# CPU_IO.net
KiCad netlist of a schematic drawn in Altium Designer
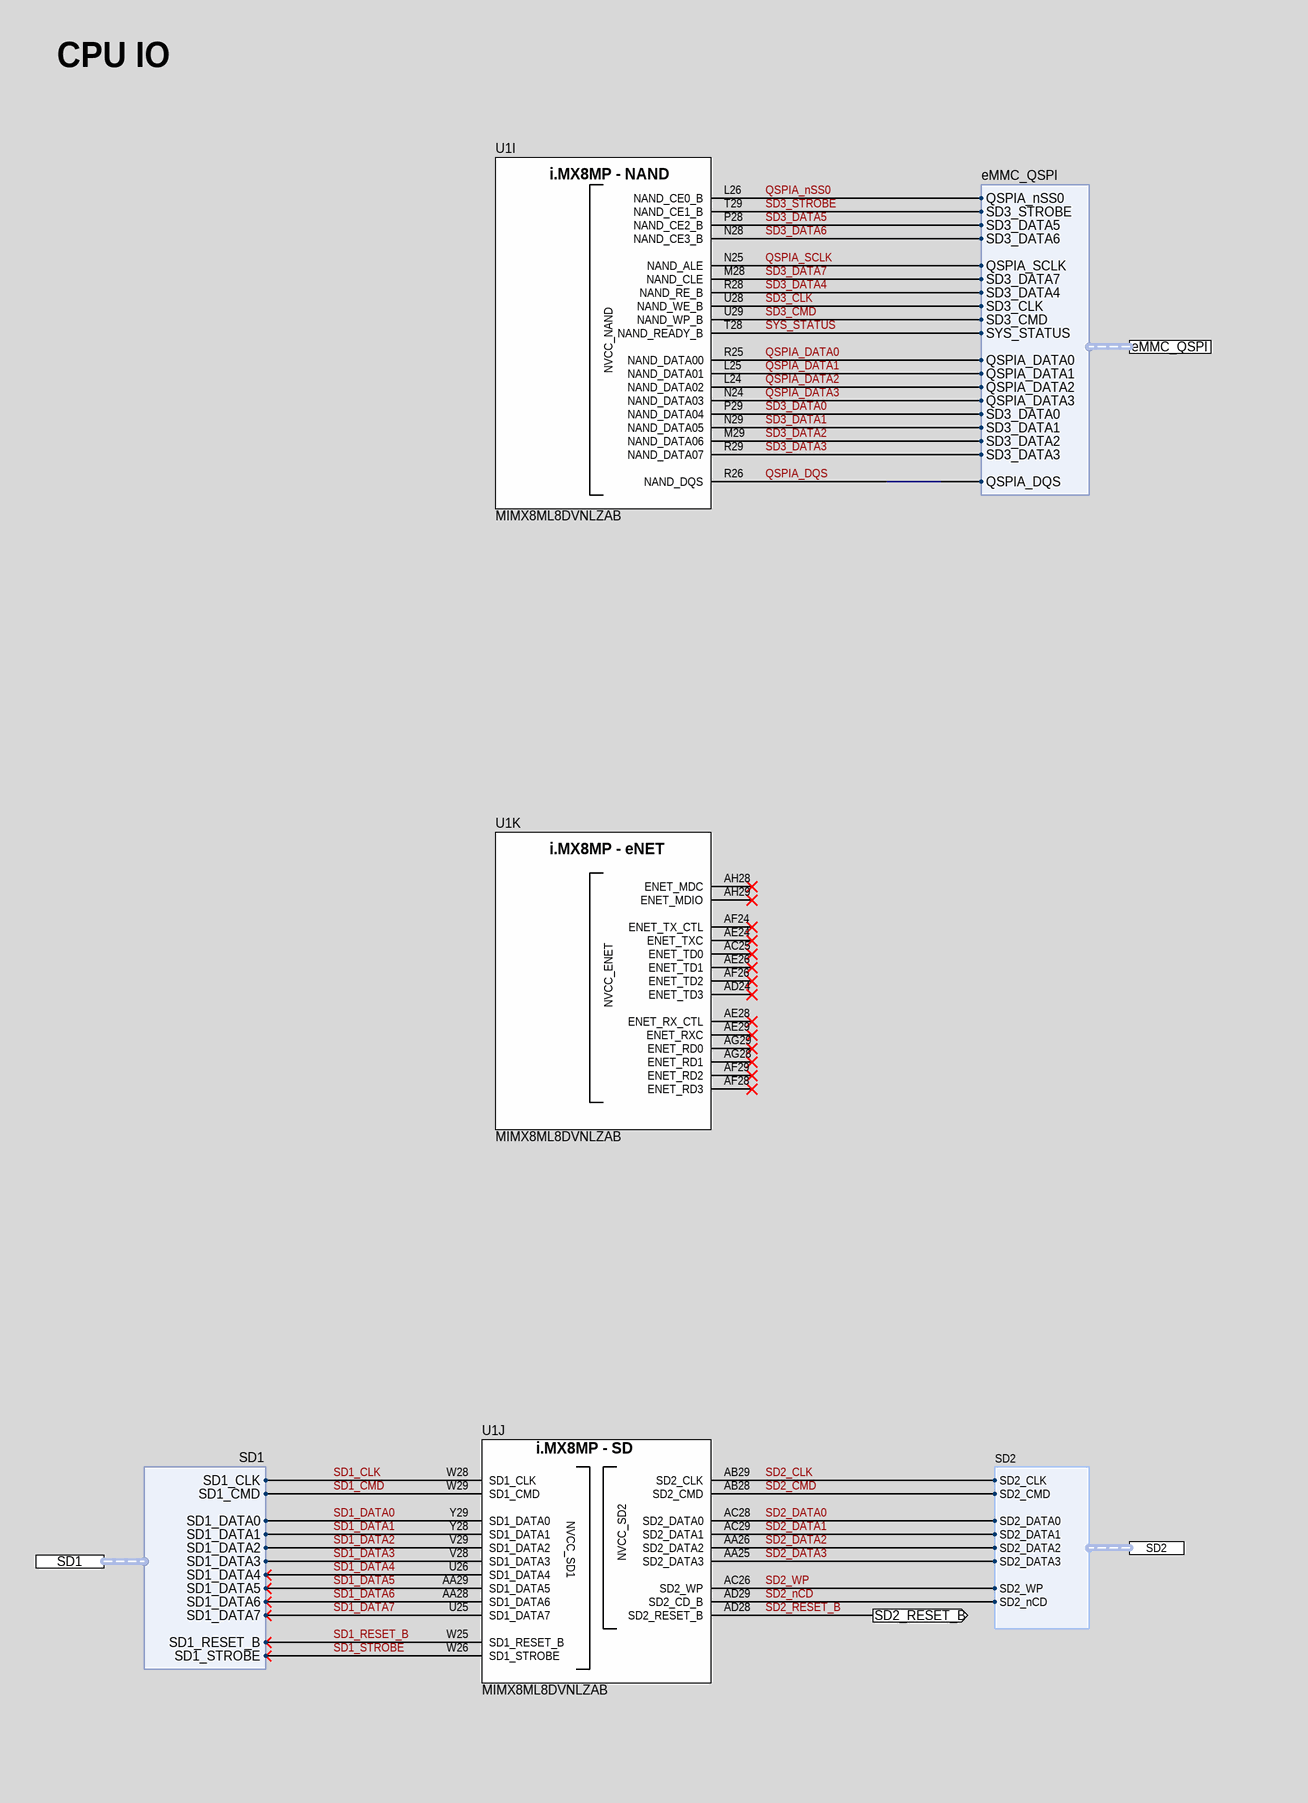
[diagram p0: CPU IO.SchDoc, left]
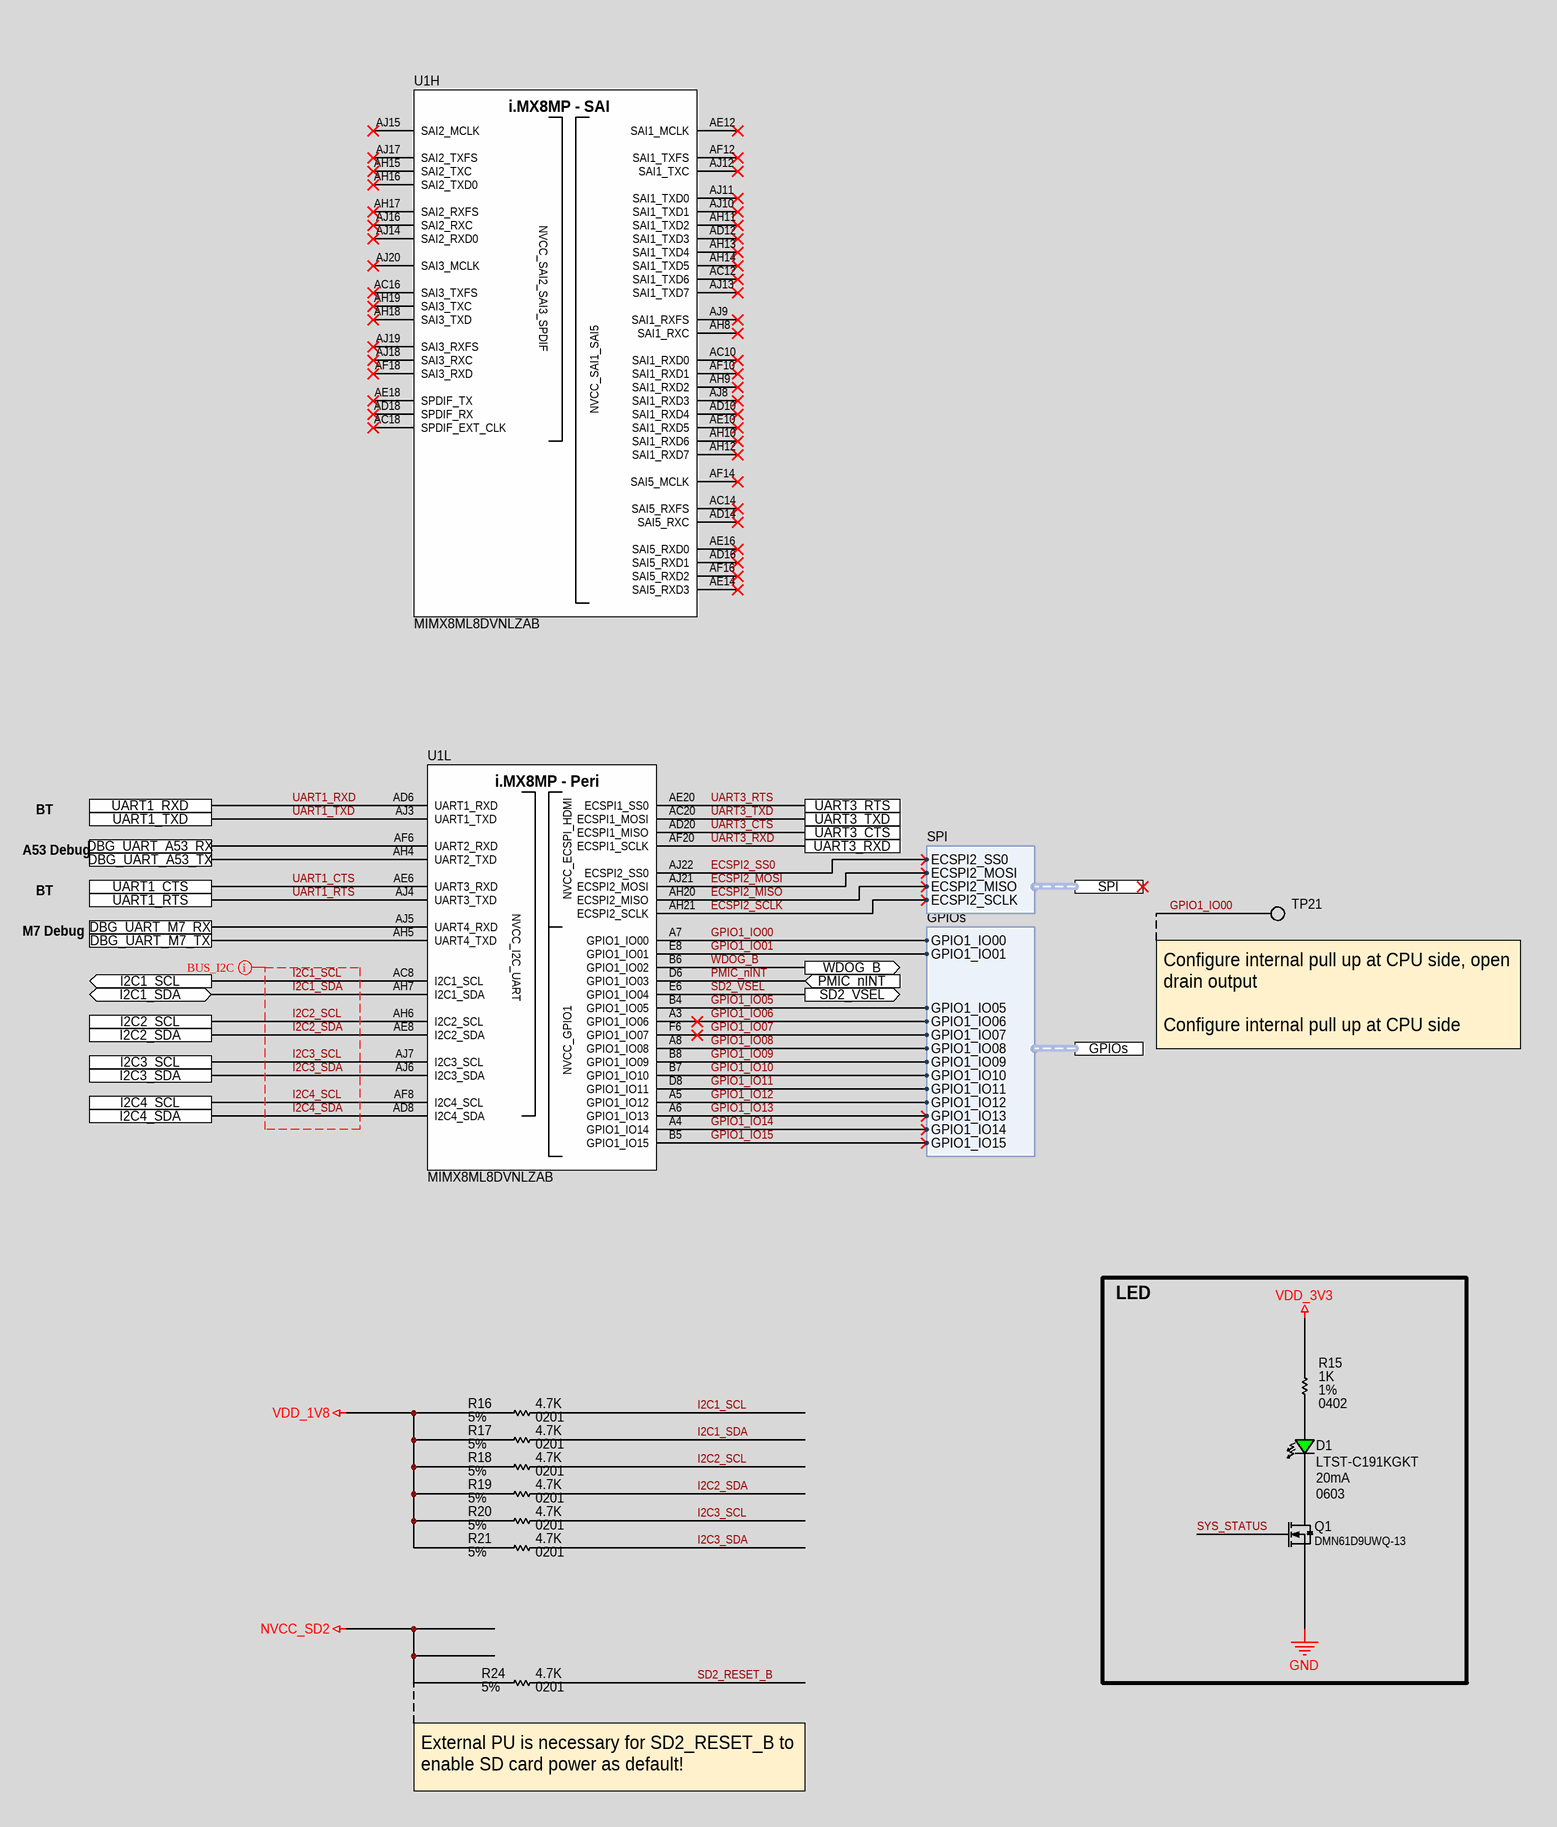
[diagram p1: CPU IO.SchDoc, right]

(export (version "E")
  (design (tool "Eeschema 10.0.6"))
  (components
    (comp (ref "D1")
      (value "LTST-C191KGKT")
      (footprint "LED_0603-GREEN")
      (description "LTST-C191KGKT Lite-On LED, green, 18-71mcd, 130, 1.9V-2.4V SMD, 0603 1.6x0.8x0.55mm RoHS")
      (fields
        (field (name "MANUFACTURER") "Vishay Lite-On")
        (field (name "TEST CURRENT") "20mA")
        (field (name "CASE/PACKAGE") "0603")
      )
      (libsource (lib "Electronic Devices_LIB") (part "LED_DIO_GREEN_20mA_0603"))
    )
    (comp (ref "Q1")
      (value "DMN61D9UWQ-13")
      (footprint "SOT-323")
      (description "N-Channel Enhancement Mode MOSFET 60V 340mA 3-Pin SOT-323 T/R")
      (fields (field (name "MANUFACTURER") "Diodes"))
      (libsource (lib "Electronic Devices_LIB") (part "TRANS_FET_CHA_N_60V_340mA"))
    )
    (comp (ref "R15")
      (value "ERJ-2RKF1001X")
      (footprint "RES_0402_RESC1005X04N")
      (description "RES SMD 1K OHM 1% 1/10W 0402")
      (fields
        (field (name "MANUFACTURER") "Panasonic")
        (field (name "RESISTANCE") "1K")
        (field (name "TOLERANCE") "1%")
        (field (name "CASE/PACKAGE") "0402")
      )
      (libsource (lib "Electronic Devices_LIB") (part "RES_1K_1%_100mW_0402"))
    )
    (comp (ref "R16")
      (value "RK73B1HTTC472J")
      (footprint "RES_0201_RESC0603X02N")
      (description "Res Thick Film 0201 4.7K Ohm 5% 0.05W(1/20W) ±200ppm/C Pad SMD Automotive T/R")
      (fields
        (field (name "MANUFACTURER") "KOA Speer")
        (field (name "TOLERANCE") "5%")
        (field (name "RESISTANCE") "4.7K")
        (field (name "CASE/PACKAGE") "0201")
      )
      (libsource (lib "Electronic Devices_LIB") (part "RES_4.7K_5%_50mW_0201"))
    )
    (comp (ref "R17")
      (value "RK73B1HTTC472J")
      (footprint "RES_0201_RESC0603X02N")
      (description "Res Thick Film 0201 4.7K Ohm 5% 0.05W(1/20W) ±200ppm/C Pad SMD Automotive T/R")
      (fields
        (field (name "MANUFACTURER") "KOA Speer")
        (field (name "TOLERANCE") "5%")
        (field (name "RESISTANCE") "4.7K")
        (field (name "CASE/PACKAGE") "0201")
      )
      (libsource (lib "Electronic Devices_LIB") (part "RES_4.7K_5%_50mW_0201"))
    )
    (comp (ref "R18")
      (value "RK73B1HTTC472J")
      (footprint "RES_0201_RESC0603X02N")
      (description "Res Thick Film 0201 4.7K Ohm 5% 0.05W(1/20W) ±200ppm/C Pad SMD Automotive T/R")
      (fields
        (field (name "MANUFACTURER") "KOA Speer")
        (field (name "TOLERANCE") "5%")
        (field (name "RESISTANCE") "4.7K")
        (field (name "CASE/PACKAGE") "0201")
      )
      (libsource (lib "Electronic Devices_LIB") (part "RES_4.7K_5%_50mW_0201"))
    )
    (comp (ref "R19")
      (value "RK73B1HTTC472J")
      (footprint "RES_0201_RESC0603X02N")
      (description "Res Thick Film 0201 4.7K Ohm 5% 0.05W(1/20W) ±200ppm/C Pad SMD Automotive T/R")
      (fields
        (field (name "MANUFACTURER") "KOA Speer")
        (field (name "TOLERANCE") "5%")
        (field (name "RESISTANCE") "4.7K")
        (field (name "CASE/PACKAGE") "0201")
      )
      (libsource (lib "Electronic Devices_LIB") (part "RES_4.7K_5%_50mW_0201"))
    )
    (comp (ref "R20")
      (value "RK73B1HTTC472J")
      (footprint "RES_0201_RESC0603X02N")
      (description "Res Thick Film 0201 4.7K Ohm 5% 0.05W(1/20W) ±200ppm/C Pad SMD Automotive T/R")
      (fields
        (field (name "MANUFACTURER") "KOA Speer")
        (field (name "TOLERANCE") "5%")
        (field (name "RESISTANCE") "4.7K")
        (field (name "CASE/PACKAGE") "0201")
      )
      (libsource (lib "Electronic Devices_LIB") (part "RES_4.7K_5%_50mW_0201"))
    )
    (comp (ref "R21")
      (value "RK73B1HTTC472J")
      (footprint "RES_0201_RESC0603X02N")
      (description "Res Thick Film 0201 4.7K Ohm 5% 0.05W(1/20W) ±200ppm/C Pad SMD Automotive T/R")
      (fields
        (field (name "MANUFACTURER") "KOA Speer")
        (field (name "TOLERANCE") "5%")
        (field (name "RESISTANCE") "4.7K")
        (field (name "CASE/PACKAGE") "0201")
      )
      (libsource (lib "Electronic Devices_LIB") (part "RES_4.7K_5%_50mW_0201"))
    )
    (comp (ref "R24")
      (value "RK73B1HTTC472J")
      (footprint "RES_0201_RESC0603X02N")
      (description "Res Thick Film 0201 4.7K Ohm 5% 0.05W(1/20W) ±200ppm/C Pad SMD Automotive T/R")
      (fields
        (field (name "MANUFACTURER") "KOA Speer")
        (field (name "TOLERANCE") "5%")
        (field (name "RESISTANCE") "4.7K")
        (field (name "CASE/PACKAGE") "0201")
      )
      (libsource (lib "Electronic Devices_LIB") (part "RES_4.7K_5%_50mW_0201"))
    )
    (comp (ref "TP21")
      (value "NO COMPONENT")
      (footprint "TP_PAD_0.5MM_SMD_ROUND")
      (description "Test Point, SMD pad, round, 1.5mm, 1.6mm, 3mm diameter")
      (libsource (lib "Electronic Devices_LIB") (part "TP_PAD_SMD_SMALL"))
    )
    (comp (ref "U1")
      (value "MIMX8ML8DVNLZAB")
      (footprint "IC_MPU_BGA548C50P29X29_1500X1500X148")
      (description "i.MX 8M Plus, Consumer, / TRAY TRAY MULTIPLE DP BAKEABLE RoHS Compliant: Yes")
      (fields (field (name "MANUFACTURER") "NXP Semiconductors"))
      (libsource (lib "Electronic Devices_LIB") (part "IC_MPU_8M_PLUS_MIMX8ML8DVNLZAB"))
    )
  )
  (nets
    (net (code "6") (name "/DBG_UART_A53_RX") (class "Default")
      (node (ref "U1") (pin "AF6") (pinfunction "UART2_RXD_AF6") (pintype "passive"))
    )
    (net (code "7") (name "/DBG_UART_A53_TX") (class "Default")
      (node (ref "U1") (pin "AH4") (pinfunction "UART2_TXD_AH4") (pintype "passive"))
    )
    (net (code "8") (name "/DBG_UART_M7_RX") (class "Default")
      (node (ref "U1") (pin "AJ5") (pinfunction "UART4_RXD_AJ5") (pintype "passive"))
    )
    (net (code "9") (name "/DBG_UART_M7_TX") (class "Default")
      (node (ref "U1") (pin "AH5") (pinfunction "UART4_TXD_AH5") (pintype "passive"))
    )
    (net (code "10") (name "/ECSPI2_MISO") (class "Default")
      (node (ref "U1") (pin "AH20") (pinfunction "ECSPI2_MISO_AH20") (pintype "passive+no_connect"))
    )
    (net (code "11") (name "/ECSPI2_MOSI") (class "Default")
      (node (ref "U1") (pin "AJ21") (pinfunction "ECSPI2_MOSI_AJ21") (pintype "passive+no_connect"))
    )
    (net (code "12") (name "/ECSPI2_SCLK") (class "Default")
      (node (ref "U1") (pin "AH21") (pinfunction "ECSPI2_SCLK_AH21") (pintype "passive+no_connect"))
    )
    (net (code "13") (name "/ECSPI2_SS0") (class "Default")
      (node (ref "U1") (pin "AJ22") (pinfunction "ECSPI2_SS0_AJ22") (pintype "passive+no_connect"))
    )
    (net (code "14") (name "/GPIO1_IO00") (class "Default")
      (node (ref "TP21") (pin "1") (pinfunction "1_1") (pintype "passive"))
      (node (ref "U1") (pin "A7") (pinfunction "GPIO1_IO00_A7") (pintype "passive"))
    )
    (net (code "15") (name "/GPIO1_IO01") (class "Default")
      (node (ref "U1") (pin "E8") (pinfunction "GPIO1_IO01_E8") (pintype "passive"))
    )
    (net (code "16") (name "/GPIO1_IO05") (class "Default")
      (node (ref "U1") (pin "B4") (pinfunction "GPIO1_IO05_B4") (pintype "passive"))
    )
    (net (code "17") (name "/GPIO1_IO06") (class "Default")
      (node (ref "U1") (pin "A3") (pinfunction "GPIO1_IO06_A3") (pintype "passive+no_connect"))
    )
    (net (code "18") (name "/GPIO1_IO07") (class "Default")
      (node (ref "U1") (pin "F6") (pinfunction "GPIO1_IO07_F6") (pintype "passive+no_connect"))
    )
    (net (code "19") (name "/GPIO1_IO08") (class "Default")
      (node (ref "U1") (pin "A8") (pinfunction "GPIO1_IO08_A8") (pintype "passive"))
    )
    (net (code "20") (name "/GPIO1_IO09") (class "Default")
      (node (ref "U1") (pin "B8") (pinfunction "GPIO1_IO09_B8") (pintype "passive"))
    )
    (net (code "21") (name "/GPIO1_IO10") (class "Default")
      (node (ref "U1") (pin "B7") (pinfunction "GPIO1_IO10_B7") (pintype "passive"))
    )
    (net (code "22") (name "/GPIO1_IO11") (class "Default")
      (node (ref "U1") (pin "D8") (pinfunction "GPIO1_IO11_D8") (pintype "passive"))
    )
    (net (code "23") (name "/GPIO1_IO12") (class "Default")
      (node (ref "U1") (pin "A5") (pinfunction "GPIO1_IO12_A5") (pintype "passive"))
    )
    (net (code "24") (name "/GPIO1_IO13") (class "Default")
      (node (ref "U1") (pin "A6") (pinfunction "GPIO1_IO13_A6") (pintype "passive+no_connect"))
    )
    (net (code "25") (name "/GPIO1_IO14") (class "Default")
      (node (ref "U1") (pin "A4") (pinfunction "GPIO1_IO14_A4") (pintype "passive+no_connect"))
    )
    (net (code "26") (name "/GPIO1_IO15") (class "Default")
      (node (ref "U1") (pin "B5") (pinfunction "GPIO1_IO15_B5") (pintype "passive+no_connect"))
    )
    (net (code "27") (name "/I2C1_SCL") (class "Default")
      (node (ref "R16") (pin "2") (pinfunction "2_2") (pintype "passive"))
      (node (ref "U1") (pin "AC8") (pinfunction "I2C1_SCL_AC8") (pintype "passive"))
    )
    (net (code "28") (name "/I2C1_SDA") (class "Default")
      (node (ref "R17") (pin "2") (pinfunction "2_2") (pintype "passive"))
      (node (ref "U1") (pin "AH7") (pinfunction "I2C1_SDA_AH7") (pintype "passive"))
    )
    (net (code "29") (name "/I2C2_SCL") (class "Default")
      (node (ref "R18") (pin "2") (pinfunction "2_2") (pintype "passive"))
      (node (ref "U1") (pin "AH6") (pinfunction "I2C2_SCL_AH6") (pintype "passive"))
    )
    (net (code "30") (name "/I2C2_SDA") (class "Default")
      (node (ref "R19") (pin "2") (pinfunction "2_2") (pintype "passive"))
      (node (ref "U1") (pin "AE8") (pinfunction "I2C2_SDA_AE8") (pintype "passive"))
    )
    (net (code "31") (name "/I2C3_SCL") (class "Default")
      (node (ref "R20") (pin "2") (pinfunction "2_2") (pintype "passive"))
      (node (ref "U1") (pin "AJ7") (pinfunction "I2C3_SCL_AJ7") (pintype "passive"))
    )
    (net (code "32") (name "/I2C3_SDA") (class "Default")
      (node (ref "R21") (pin "2") (pinfunction "2_2") (pintype "passive"))
      (node (ref "U1") (pin "AJ6") (pinfunction "I2C3_SDA_AJ6") (pintype "passive"))
    )
    (net (code "33") (name "/I2C4_SCL") (class "Default")
      (node (ref "U1") (pin "AF8") (pinfunction "I2C4_SCL_AF8") (pintype "passive"))
    )
    (net (code "34") (name "/I2C4_SDA") (class "Default")
      (node (ref "U1") (pin "AD8") (pinfunction "I2C4_SDA_AD8") (pintype "passive"))
    )
    (net (code "35") (name "/PMIC_nINT") (class "Default")
      (node (ref "U1") (pin "D6") (pinfunction "GPIO1_IO03_D6") (pintype "passive"))
    )
    (net (code "36") (name "/QSPIA_DATA0") (class "Default")
      (node (ref "U1") (pin "R25") (pinfunction "NAND_DATA00_R25") (pintype "passive"))
    )
    (net (code "37") (name "/QSPIA_DATA1") (class "Default")
      (node (ref "U1") (pin "L25") (pinfunction "NAND_DATA01_L25") (pintype "passive"))
    )
    (net (code "38") (name "/QSPIA_DATA2") (class "Default")
      (node (ref "U1") (pin "L24") (pinfunction "NAND_DATA02_L24") (pintype "passive"))
    )
    (net (code "39") (name "/QSPIA_DATA3") (class "Default")
      (node (ref "U1") (pin "N24") (pinfunction "NAND_DATA03_N24") (pintype "passive"))
    )
    (net (code "40") (name "/QSPIA_DQS") (class "Default")
      (node (ref "U1") (pin "R26") (pinfunction "NAND_DQS_R26") (pintype "passive"))
    )
    (net (code "41") (name "/QSPIA_SCLK") (class "Default")
      (node (ref "U1") (pin "N25") (pinfunction "NAND_ALE_N25") (pintype "passive"))
    )
    (net (code "42") (name "/QSPIA_nSS0") (class "Default")
      (node (ref "U1") (pin "L26") (pinfunction "NAND_CE0_B_L26") (pintype "passive"))
    )
    (net (code "43") (name "/SD1_CLK") (class "Default")
      (node (ref "U1") (pin "W28") (pinfunction "SD1_CLK_W28") (pintype "passive"))
    )
    (net (code "44") (name "/SD1_CMD") (class "Default")
      (node (ref "U1") (pin "W29") (pinfunction "SD1_CMD_W29") (pintype "passive"))
    )
    (net (code "45") (name "/SD1_DATA0") (class "Default")
      (node (ref "U1") (pin "Y29") (pinfunction "SD1_DATA0_Y29") (pintype "passive"))
    )
    (net (code "46") (name "/SD1_DATA1") (class "Default")
      (node (ref "U1") (pin "Y28") (pinfunction "SD1_DATA1_Y28") (pintype "passive"))
    )
    (net (code "47") (name "/SD1_DATA2") (class "Default")
      (node (ref "U1") (pin "V29") (pinfunction "SD1_DATA2_V29") (pintype "passive"))
    )
    (net (code "48") (name "/SD1_DATA3") (class "Default")
      (node (ref "U1") (pin "V28") (pinfunction "SD1_DATA3_V28") (pintype "passive"))
    )
    (net (code "49") (name "/SD1_DATA4") (class "Default")
      (node (ref "U1") (pin "U26") (pinfunction "SD1_DATA4_U26") (pintype "passive+no_connect"))
    )
    (net (code "50") (name "/SD1_DATA5") (class "Default")
      (node (ref "U1") (pin "AA29") (pinfunction "SD1_DATA5_AA29") (pintype "passive+no_connect"))
    )
    (net (code "51") (name "/SD1_DATA6") (class "Default")
      (node (ref "U1") (pin "AA28") (pinfunction "SD1_DATA6_AA28") (pintype "passive+no_connect"))
    )
    (net (code "52") (name "/SD1_DATA7") (class "Default")
      (node (ref "U1") (pin "U25") (pinfunction "SD1_DATA7_U25") (pintype "passive+no_connect"))
    )
    (net (code "53") (name "/SD1_RESET_B") (class "Default")
      (node (ref "U1") (pin "W25") (pinfunction "SD1_RESET_B_W25") (pintype "passive+no_connect"))
    )
    (net (code "54") (name "/SD1_STROBE") (class "Default")
      (node (ref "U1") (pin "W26") (pinfunction "SD1_STROBE_W26") (pintype "passive+no_connect"))
    )
    (net (code "55") (name "/SD2_CLK") (class "Default")
      (node (ref "U1") (pin "AB29") (pinfunction "SD2_CLK_AB29") (pintype "passive"))
    )
    (net (code "56") (name "/SD2_CMD") (class "Default")
      (node (ref "U1") (pin "AB28") (pinfunction "SD2_CMD_AB28") (pintype "passive"))
    )
    (net (code "57") (name "/SD2_DATA0") (class "Default")
      (node (ref "U1") (pin "AC28") (pinfunction "SD2_DATA0_AC28") (pintype "passive"))
    )
    (net (code "58") (name "/SD2_DATA1") (class "Default")
      (node (ref "U1") (pin "AC29") (pinfunction "SD2_DATA1_AC29") (pintype "passive"))
    )
    (net (code "59") (name "/SD2_DATA2") (class "Default")
      (node (ref "U1") (pin "AA26") (pinfunction "SD2_DATA2_AA26") (pintype "passive"))
    )
    (net (code "60") (name "/SD2_DATA3") (class "Default")
      (node (ref "U1") (pin "AA25") (pinfunction "SD2_DATA3_AA25") (pintype "passive"))
    )
    (net (code "61") (name "/SD2_RESET_B") (class "Default")
      (node (ref "R24") (pin "2") (pinfunction "2_2") (pintype "passive"))
      (node (ref "U1") (pin "AD28") (pinfunction "SD2_RESET_B_AD28") (pintype "passive"))
    )
    (net (code "62") (name "/SD2_VSEL") (class "Default")
      (node (ref "U1") (pin "E6") (pinfunction "GPIO1_IO04_E6") (pintype "passive"))
    )
    (net (code "63") (name "/SD2_WP") (class "Default")
      (node (ref "U1") (pin "AC26") (pinfunction "SD2_WP_AC26") (pintype "passive"))
    )
    (net (code "64") (name "/SD2_nCD") (class "Default")
      (node (ref "U1") (pin "AD29") (pinfunction "SD2_CD_B_AD29") (pintype "passive"))
    )
    (net (code "65") (name "/SD3_CLK") (class "Default")
      (node (ref "U1") (pin "U28") (pinfunction "NAND_WE_B_U28") (pintype "passive"))
    )
    (net (code "66") (name "/SD3_CMD") (class "Default")
      (node (ref "U1") (pin "U29") (pinfunction "NAND_WP_B_U29") (pintype "passive"))
    )
    (net (code "67") (name "/SD3_DATA0") (class "Default")
      (node (ref "U1") (pin "P29") (pinfunction "NAND_DATA04_P29") (pintype "passive"))
    )
    (net (code "68") (name "/SD3_DATA1") (class "Default")
      (node (ref "U1") (pin "N29") (pinfunction "NAND_DATA05_N29") (pintype "passive"))
    )
    (net (code "69") (name "/SD3_DATA2") (class "Default")
      (node (ref "U1") (pin "M29") (pinfunction "NAND_DATA06_M29") (pintype "passive"))
    )
    (net (code "70") (name "/SD3_DATA3") (class "Default")
      (node (ref "U1") (pin "R29") (pinfunction "NAND_DATA07_R29") (pintype "passive"))
    )
    (net (code "71") (name "/SD3_DATA4") (class "Default")
      (node (ref "U1") (pin "R28") (pinfunction "NAND_RE_B_R28") (pintype "passive"))
    )
    (net (code "72") (name "/SD3_DATA5") (class "Default")
      (node (ref "U1") (pin "P28") (pinfunction "NAND_CE2_B_P28") (pintype "passive"))
    )
    (net (code "73") (name "/SD3_DATA6") (class "Default")
      (node (ref "U1") (pin "N28") (pinfunction "NAND_CE3_B_N28") (pintype "passive"))
    )
    (net (code "74") (name "/SD3_DATA7") (class "Default")
      (node (ref "U1") (pin "M28") (pinfunction "NAND_CLE_M28") (pintype "passive"))
    )
    (net (code "75") (name "/SD3_STROBE") (class "Default")
      (node (ref "U1") (pin "T29") (pinfunction "NAND_CE1_B_T29") (pintype "passive"))
    )
    (net (code "76") (name "/SYS_STATUS") (class "Default")
      (node (ref "Q1") (pin "G") (pinfunction "G_G") (pintype "passive"))
      (node (ref "U1") (pin "T28") (pinfunction "NAND_READY_B_T28") (pintype "passive"))
    )
    (net (code "77") (name "/UART1_CTS") (class "Default")
      (node (ref "U1") (pin "AE6") (pinfunction "UART3_RXD_AE6") (pintype "passive"))
    )
    (net (code "78") (name "/UART1_RTS") (class "Default")
      (node (ref "U1") (pin "AJ4") (pinfunction "UART3_TXD_AJ4") (pintype "passive"))
    )
    (net (code "79") (name "/UART1_RXD") (class "Default")
      (node (ref "U1") (pin "AD6") (pinfunction "UART1_RXD_AD6") (pintype "passive"))
    )
    (net (code "80") (name "/UART1_TXD") (class "Default")
      (node (ref "U1") (pin "AJ3") (pinfunction "UART1_TXD_AJ3") (pintype "passive"))
    )
    (net (code "81") (name "/UART3_CTS") (class "Default")
      (node (ref "U1") (pin "AD20") (pinfunction "ECSPI1_MISO_AD20") (pintype "passive"))
    )
    (net (code "82") (name "/UART3_RTS") (class "Default")
      (node (ref "U1") (pin "AE20") (pinfunction "ECSPI1_SS0_AE20") (pintype "passive"))
    )
    (net (code "83") (name "/UART3_RXD") (class "Default")
      (node (ref "U1") (pin "AF20") (pinfunction "ECSPI1_SCLK_AF20") (pintype "passive"))
    )
    (net (code "84") (name "/UART3_TXD") (class "Default")
      (node (ref "U1") (pin "AC20") (pinfunction "ECSPI1_MOSI_AC20") (pintype "passive"))
    )
    (net (code "85") (name "/WDOG_B") (class "Default")
      (node (ref "U1") (pin "B6") (pinfunction "GPIO1_IO02_B6") (pintype "passive"))
    )
    (net (code "91") (name "GND") (class "Default")
      (node (ref "Q1") (pin "S") (pinfunction "S_S") (pintype "passive"))
    )
    (net (code "92") (name "NVCC_SD2") (class "Default")
      (node (ref "R24") (pin "1") (pinfunction "1_1") (pintype "passive"))
    )
    (net (code "93") (name "Net-(D1-A)") (class "Default")
      (node (ref "D1") (pin "2") (pinfunction "A_2") (pintype "passive"))
      (node (ref "R15") (pin "1") (pinfunction "1_1") (pintype "passive"))
    )
    (net (code "94") (name "Net-(D1-C)") (class "Default")
      (node (ref "D1") (pin "1") (pinfunction "C_1") (pintype "passive"))
      (node (ref "Q1") (pin "D") (pinfunction "D_D") (pintype "passive"))
    )
    (net (code "95") (name "VDD_1V8") (class "Default")
      (node (ref "R16") (pin "1") (pinfunction "1_1") (pintype "passive"))
      (node (ref "R17") (pin "1") (pinfunction "1_1") (pintype "passive"))
      (node (ref "R18") (pin "1") (pinfunction "1_1") (pintype "passive"))
      (node (ref "R19") (pin "1") (pinfunction "1_1") (pintype "passive"))
      (node (ref "R20") (pin "1") (pinfunction "1_1") (pintype "passive"))
      (node (ref "R21") (pin "1") (pinfunction "1_1") (pintype "passive"))
    )
    (net (code "96") (name "VDD_3V3") (class "Default")
      (node (ref "R15") (pin "2") (pinfunction "2_2") (pintype "passive"))
    )
    (net (code "97") (name "unconnected-(U1H-SAI1_MCLK-PadAE12)") (class "Default")
      (node (ref "U1") (pin "AE12") (pinfunction "SAI1_MCLK_AE12") (pintype "passive+no_connect"))
    )
    (net (code "98") (name "unconnected-(U1H-SAI1_RXC-PadAH8)") (class "Default")
      (node (ref "U1") (pin "AH8") (pinfunction "SAI1_RXC_AH8") (pintype "passive+no_connect"))
    )
    (net (code "99") (name "unconnected-(U1H-SAI1_RXD0-PadAC10)") (class "Default")
      (node (ref "U1") (pin "AC10") (pinfunction "SAI1_RXD0_AC10") (pintype "passive+no_connect"))
    )
    (net (code "100") (name "unconnected-(U1H-SAI1_RXD1-PadAF10)") (class "Default")
      (node (ref "U1") (pin "AF10") (pinfunction "SAI1_RXD1_AF10") (pintype "passive+no_connect"))
    )
    (net (code "101") (name "unconnected-(U1H-SAI1_RXD2-PadAH9)") (class "Default")
      (node (ref "U1") (pin "AH9") (pinfunction "SAI1_RXD2_AH9") (pintype "passive+no_connect"))
    )
    (net (code "102") (name "unconnected-(U1H-SAI1_RXD3-PadAJ8)") (class "Default")
      (node (ref "U1") (pin "AJ8") (pinfunction "SAI1_RXD3_AJ8") (pintype "passive+no_connect"))
    )
    (net (code "103") (name "unconnected-(U1H-SAI1_RXD4-PadAD10)") (class "Default")
      (node (ref "U1") (pin "AD10") (pinfunction "SAI1_RXD4_AD10") (pintype "passive+no_connect"))
    )
    (net (code "104") (name "unconnected-(U1H-SAI1_RXD5-PadAE10)") (class "Default")
      (node (ref "U1") (pin "AE10") (pinfunction "SAI1_RXD5_AE10") (pintype "passive+no_connect"))
    )
    (net (code "105") (name "unconnected-(U1H-SAI1_RXD6-PadAH10)") (class "Default")
      (node (ref "U1") (pin "AH10") (pinfunction "SAI1_RXD6_AH10") (pintype "passive+no_connect"))
    )
    (net (code "106") (name "unconnected-(U1H-SAI1_RXD7-PadAH12)") (class "Default")
      (node (ref "U1") (pin "AH12") (pinfunction "SAI1_RXD7_AH12") (pintype "passive+no_connect"))
    )
    (net (code "107") (name "unconnected-(U1H-SAI1_RXFS-PadAJ9)") (class "Default")
      (node (ref "U1") (pin "AJ9") (pinfunction "SAI1_RXFS_AJ9") (pintype "passive+no_connect"))
    )
    (net (code "108") (name "unconnected-(U1H-SAI1_TXC-PadAJ12)") (class "Default")
      (node (ref "U1") (pin "AJ12") (pinfunction "SAI1_TXC_AJ12") (pintype "passive+no_connect"))
    )
    (net (code "109") (name "unconnected-(U1H-SAI1_TXD0-PadAJ11)") (class "Default")
      (node (ref "U1") (pin "AJ11") (pinfunction "SAI1_TXD0_AJ11") (pintype "passive+no_connect"))
    )
    (net (code "110") (name "unconnected-(U1H-SAI1_TXD1-PadAJ10)") (class "Default")
      (node (ref "U1") (pin "AJ10") (pinfunction "SAI1_TXD1_AJ10") (pintype "passive+no_connect"))
    )
    (net (code "111") (name "unconnected-(U1H-SAI1_TXD2-PadAH11)") (class "Default")
      (node (ref "U1") (pin "AH11") (pinfunction "SAI1_TXD2_AH11") (pintype "passive+no_connect"))
    )
    (net (code "112") (name "unconnected-(U1H-SAI1_TXD3-PadAD12)") (class "Default")
      (node (ref "U1") (pin "AD12") (pinfunction "SAI1_TXD3_AD12") (pintype "passive+no_connect"))
    )
    (net (code "113") (name "unconnected-(U1H-SAI1_TXD4-PadAH13)") (class "Default")
      (node (ref "U1") (pin "AH13") (pinfunction "SAI1_TXD4_AH13") (pintype "passive+no_connect"))
    )
    (net (code "114") (name "unconnected-(U1H-SAI1_TXD5-PadAH14)") (class "Default")
      (node (ref "U1") (pin "AH14") (pinfunction "SAI1_TXD5_AH14") (pintype "passive+no_connect"))
    )
    (net (code "115") (name "unconnected-(U1H-SAI1_TXD6-PadAC12)") (class "Default")
      (node (ref "U1") (pin "AC12") (pinfunction "SAI1_TXD6_AC12") (pintype "passive+no_connect"))
    )
    (net (code "116") (name "unconnected-(U1H-SAI1_TXD7-PadAJ13)") (class "Default")
      (node (ref "U1") (pin "AJ13") (pinfunction "SAI1_TXD7_AJ13") (pintype "passive+no_connect"))
    )
    (net (code "117") (name "unconnected-(U1H-SAI1_TXFS-PadAF12)") (class "Default")
      (node (ref "U1") (pin "AF12") (pinfunction "SAI1_TXFS_AF12") (pintype "passive+no_connect"))
    )
    (net (code "118") (name "unconnected-(U1H-SAI2_MCLK-PadAJ15)") (class "Default")
      (node (ref "U1") (pin "AJ15") (pinfunction "SAI2_MCLK_AJ15") (pintype "passive+no_connect"))
    )
    (net (code "119") (name "unconnected-(U1H-SAI2_RXC-PadAJ16)") (class "Default")
      (node (ref "U1") (pin "AJ16") (pinfunction "SAI2_RXC_AJ16") (pintype "passive+no_connect"))
    )
    (net (code "120") (name "unconnected-(U1H-SAI2_RXD0-PadAJ14)") (class "Default")
      (node (ref "U1") (pin "AJ14") (pinfunction "SAI2_RXD0_AJ14") (pintype "passive+no_connect"))
    )
    (net (code "121") (name "unconnected-(U1H-SAI2_RXFS-PadAH17)") (class "Default")
      (node (ref "U1") (pin "AH17") (pinfunction "SAI2_RXFS_AH17") (pintype "passive+no_connect"))
    )
    (net (code "122") (name "unconnected-(U1H-SAI2_TXC-PadAH15)") (class "Default")
      (node (ref "U1") (pin "AH15") (pinfunction "SAI2_TXC_AH15") (pintype "passive+no_connect"))
    )
    (net (code "123") (name "unconnected-(U1H-SAI2_TXD0-PadAH16)") (class "Default")
      (node (ref "U1") (pin "AH16") (pinfunction "SAI2_TXD0_AH16") (pintype "passive+no_connect"))
    )
    (net (code "124") (name "unconnected-(U1H-SAI2_TXFS-PadAJ17)") (class "Default")
      (node (ref "U1") (pin "AJ17") (pinfunction "SAI2_TXFS_AJ17") (pintype "passive+no_connect"))
    )
    (net (code "125") (name "unconnected-(U1H-SAI3_MCLK-PadAJ20)") (class "Default")
      (node (ref "U1") (pin "AJ20") (pinfunction "SAI3_MCLK_AJ20") (pintype "passive+no_connect"))
    )
    (net (code "126") (name "unconnected-(U1H-SAI3_RXC-PadAJ18)") (class "Default")
      (node (ref "U1") (pin "AJ18") (pinfunction "SAI3_RXC_AJ18") (pintype "passive+no_connect"))
    )
    (net (code "127") (name "unconnected-(U1H-SAI3_RXD-PadAF18)") (class "Default")
      (node (ref "U1") (pin "AF18") (pinfunction "SAI3_RXD_AF18") (pintype "passive+no_connect"))
    )
    (net (code "128") (name "unconnected-(U1H-SAI3_RXFS-PadAJ19)") (class "Default")
      (node (ref "U1") (pin "AJ19") (pinfunction "SAI3_RXFS_AJ19") (pintype "passive+no_connect"))
    )
    (net (code "129") (name "unconnected-(U1H-SAI3_TXC-PadAH19)") (class "Default")
      (node (ref "U1") (pin "AH19") (pinfunction "SAI3_TXC_AH19") (pintype "passive+no_connect"))
    )
    (net (code "130") (name "unconnected-(U1H-SAI3_TXD-PadAH18)") (class "Default")
      (node (ref "U1") (pin "AH18") (pinfunction "SAI3_TXD_AH18") (pintype "passive+no_connect"))
    )
    (net (code "131") (name "unconnected-(U1H-SAI3_TXFS-PadAC16)") (class "Default")
      (node (ref "U1") (pin "AC16") (pinfunction "SAI3_TXFS_AC16") (pintype "passive+no_connect"))
    )
    (net (code "132") (name "unconnected-(U1H-SAI5_MCLK-PadAF14)") (class "Default")
      (node (ref "U1") (pin "AF14") (pinfunction "SAI5_MCLK_AF14") (pintype "passive+no_connect"))
    )
    (net (code "133") (name "unconnected-(U1H-SAI5_RXC-PadAD14)") (class "Default")
      (node (ref "U1") (pin "AD14") (pinfunction "SAI5_RXC_AD14") (pintype "passive+no_connect"))
    )
    (net (code "134") (name "unconnected-(U1H-SAI5_RXD0-PadAE16)") (class "Default")
      (node (ref "U1") (pin "AE16") (pinfunction "SAI5_RXD0_AE16") (pintype "passive+no_connect"))
    )
    (net (code "135") (name "unconnected-(U1H-SAI5_RXD1-PadAD16)") (class "Default")
      (node (ref "U1") (pin "AD16") (pinfunction "SAI5_RXD1_AD16") (pintype "passive+no_connect"))
    )
    (net (code "136") (name "unconnected-(U1H-SAI5_RXD2-PadAF16)") (class "Default")
      (node (ref "U1") (pin "AF16") (pinfunction "SAI5_RXD2_AF16") (pintype "passive+no_connect"))
    )
    (net (code "137") (name "unconnected-(U1H-SAI5_RXD3-PadAE14)") (class "Default")
      (node (ref "U1") (pin "AE14") (pinfunction "SAI5_RXD3_AE14") (pintype "passive+no_connect"))
    )
    (net (code "138") (name "unconnected-(U1H-SAI5_RXFS-PadAC14)") (class "Default")
      (node (ref "U1") (pin "AC14") (pinfunction "SAI5_RXFS_AC14") (pintype "passive+no_connect"))
    )
    (net (code "139") (name "unconnected-(U1H-SPDIF_EXT_CLK-PadAC18)") (class "Default")
      (node (ref "U1") (pin "AC18") (pinfunction "SPDIF_EXT_CLK_AC18") (pintype "passive+no_connect"))
    )
    (net (code "140") (name "unconnected-(U1H-SPDIF_RX-PadAD18)") (class "Default")
      (node (ref "U1") (pin "AD18") (pinfunction "SPDIF_RX_AD18") (pintype "passive+no_connect"))
    )
    (net (code "141") (name "unconnected-(U1H-SPDIF_TX-PadAE18)") (class "Default")
      (node (ref "U1") (pin "AE18") (pinfunction "SPDIF_TX_AE18") (pintype "passive+no_connect"))
    )
    (net (code "142") (name "unconnected-(U1K-ENET_MDC-PadAH28)") (class "Default")
      (node (ref "U1") (pin "AH28") (pinfunction "ENET_MDC_AH28") (pintype "passive+no_connect"))
    )
    (net (code "143") (name "unconnected-(U1K-ENET_MDIO-PadAH29)") (class "Default")
      (node (ref "U1") (pin "AH29") (pinfunction "ENET_MDIO_AH29") (pintype "passive+no_connect"))
    )
    (net (code "144") (name "unconnected-(U1K-ENET_RD0-PadAG29)") (class "Default")
      (node (ref "U1") (pin "AG29") (pinfunction "ENET_RD0_AG29") (pintype "passive+no_connect"))
    )
    (net (code "145") (name "unconnected-(U1K-ENET_RD1-PadAG28)") (class "Default")
      (node (ref "U1") (pin "AG28") (pinfunction "ENET_RD1_AG28") (pintype "passive+no_connect"))
    )
    (net (code "146") (name "unconnected-(U1K-ENET_RD2-PadAF29)") (class "Default")
      (node (ref "U1") (pin "AF29") (pinfunction "ENET_RD2_AF29") (pintype "passive+no_connect"))
    )
    (net (code "147") (name "unconnected-(U1K-ENET_RD3-PadAF28)") (class "Default")
      (node (ref "U1") (pin "AF28") (pinfunction "ENET_RD3_AF28") (pintype "passive+no_connect"))
    )
    (net (code "148") (name "unconnected-(U1K-ENET_RXC-PadAE29)") (class "Default")
      (node (ref "U1") (pin "AE29") (pinfunction "ENET_RXC_AE29") (pintype "passive+no_connect"))
    )
    (net (code "149") (name "unconnected-(U1K-ENET_RX_CTL-PadAE28)") (class "Default")
      (node (ref "U1") (pin "AE28") (pinfunction "ENET_RX_CTL_AE28") (pintype "passive+no_connect"))
    )
    (net (code "150") (name "unconnected-(U1K-ENET_TD0-PadAC25)") (class "Default")
      (node (ref "U1") (pin "AC25") (pinfunction "ENET_TD0_AC25") (pintype "passive+no_connect"))
    )
    (net (code "151") (name "unconnected-(U1K-ENET_TD1-PadAE26)") (class "Default")
      (node (ref "U1") (pin "AE26") (pinfunction "ENET_TD1_AE26") (pintype "passive+no_connect"))
    )
    (net (code "152") (name "unconnected-(U1K-ENET_TD2-PadAF26)") (class "Default")
      (node (ref "U1") (pin "AF26") (pinfunction "ENET_TD2_AF26") (pintype "passive+no_connect"))
    )
    (net (code "153") (name "unconnected-(U1K-ENET_TD3-PadAD24)") (class "Default")
      (node (ref "U1") (pin "AD24") (pinfunction "ENET_TD3_AD24") (pintype "passive+no_connect"))
    )
    (net (code "154") (name "unconnected-(U1K-ENET_TXC-PadAE24)") (class "Default")
      (node (ref "U1") (pin "AE24") (pinfunction "ENET_TXC_AE24") (pintype "passive+no_connect"))
    )
    (net (code "155") (name "unconnected-(U1K-ENET_TX_CTL-PadAF24)") (class "Default")
      (node (ref "U1") (pin "AF24") (pinfunction "ENET_TX_CTL_AF24") (pintype "passive+no_connect"))
    )
  )
)
